# SSCI_SPI_LCD.net
KiCad netlist of a schematic drawn in EAGLE
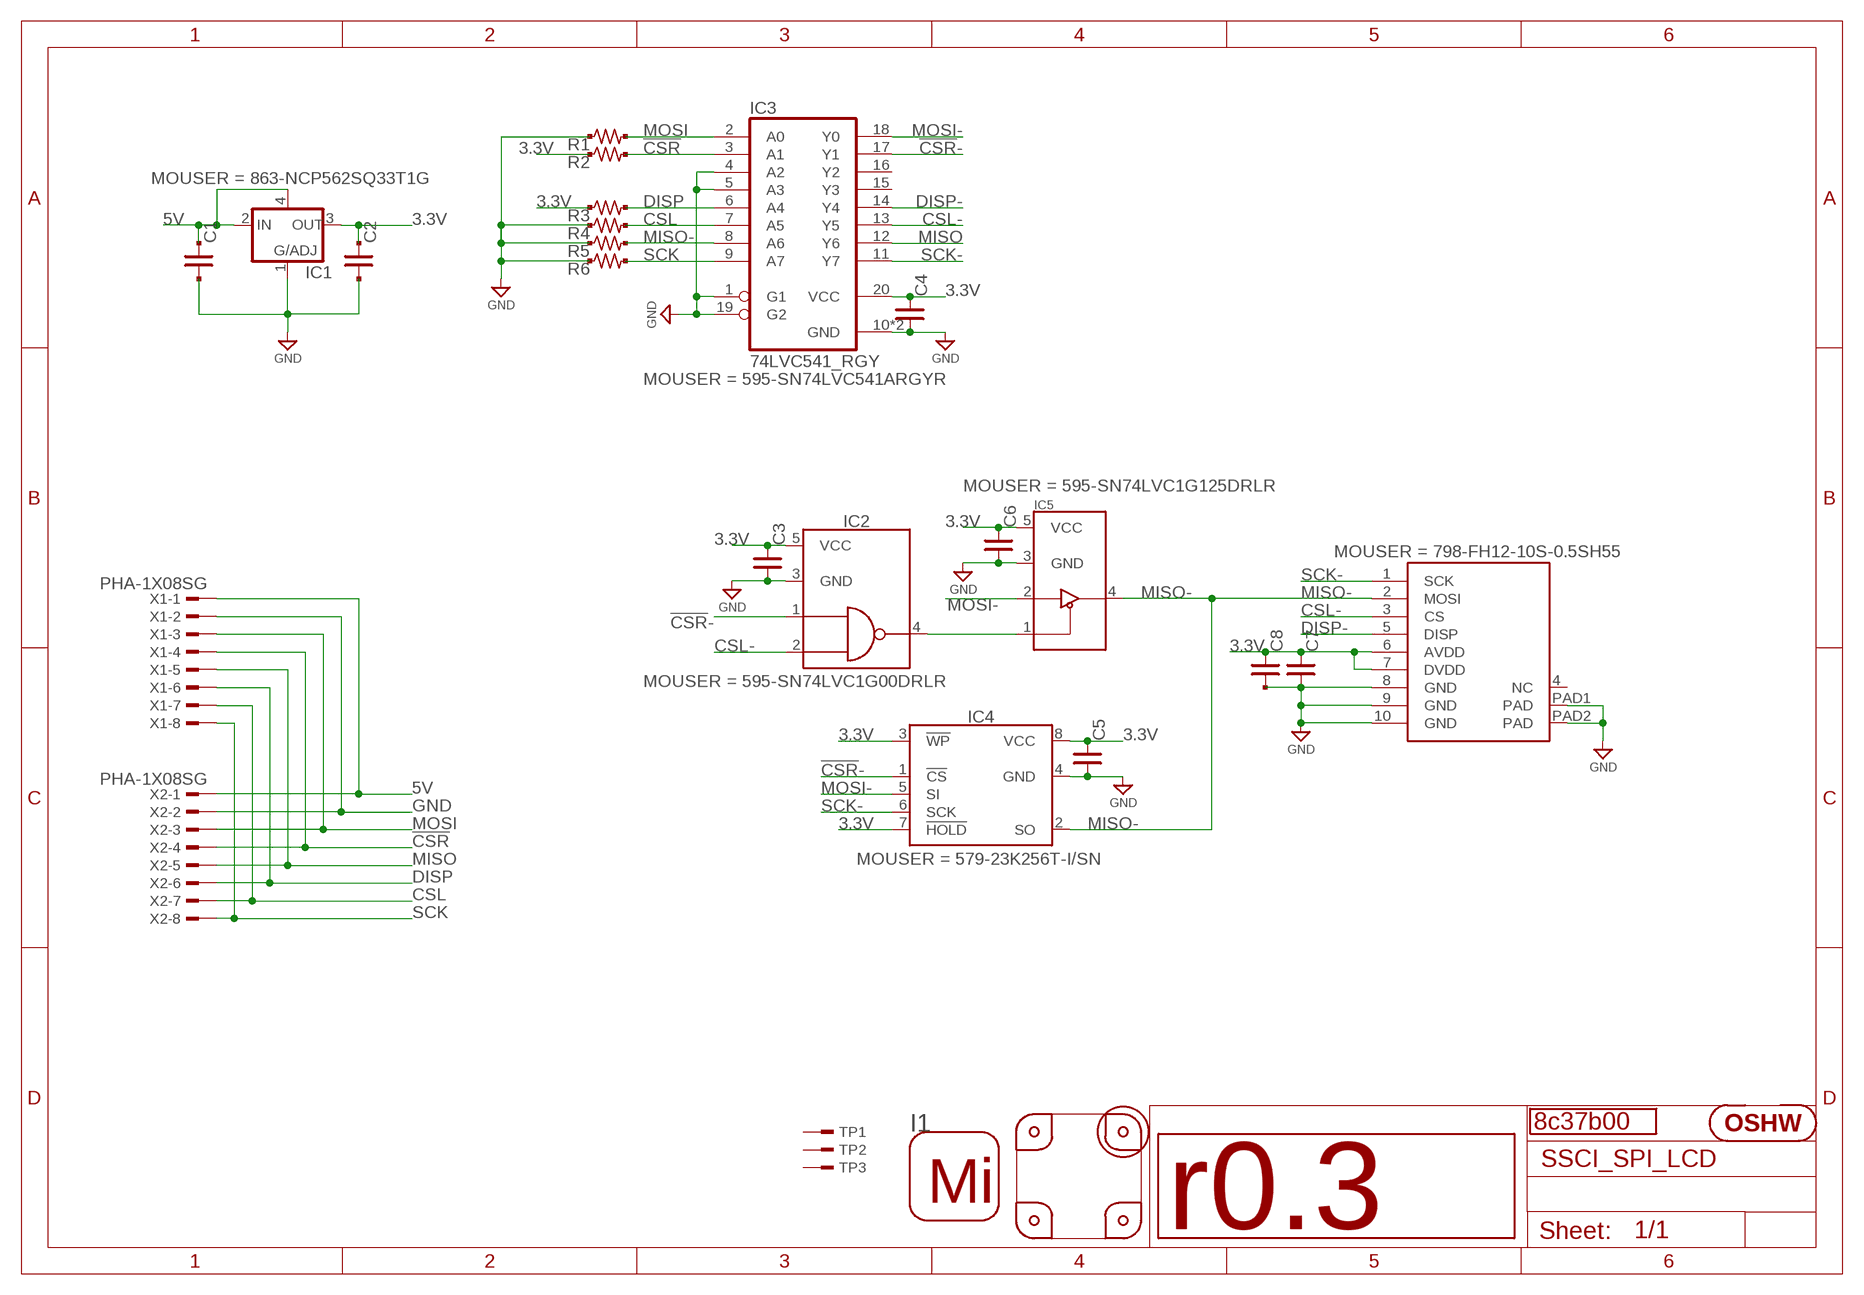
[diagram p0: schematic, sheet 1]

(export (version "E")
  (design (tool "Eeschema 10.0.6"))
  (components
    (comp (ref "C1")
      (value "C_SMD_10U_1608")
      (footprint "eagle-import:CR_1608")
      (libsource (lib "eagle-import") (part "C_SMD__160810U"))
    )
    (comp (ref "C2")
      (value "C_SMD_10U_1608")
      (footprint "eagle-import:CR_1608")
      (libsource (lib "eagle-import") (part "C_SMD__160810U"))
    )
    (comp (ref "C3")
      (value "C_SMD_0.1U_1005")
      (footprint "eagle-import:C0402")
      (libsource (lib "eagle-import") (part "C_SMD__10050.1U"))
    )
    (comp (ref "C4")
      (value "C_SMD_0.1U_1005")
      (footprint "eagle-import:C0402")
      (libsource (lib "eagle-import") (part "C_SMD__10050.1U"))
    )
    (comp (ref "C5")
      (value "C_SMD_0.1U_1005")
      (footprint "eagle-import:C0402")
      (libsource (lib "eagle-import") (part "C_SMD__10050.1U"))
    )
    (comp (ref "C6")
      (value "C_SMD_0.1U_1005")
      (footprint "eagle-import:C0402")
      (libsource (lib "eagle-import") (part "C_SMD__10050.1U"))
    )
    (comp (ref "C7")
      (value "C_SMD_0.1U_1005")
      (footprint "eagle-import:C0402")
      (libsource (lib "eagle-import") (part "C_SMD__10050.1U"))
    )
    (comp (ref "C8")
      (value "C_SMD_0.1U_1005")
      (footprint "eagle-import:C0402")
      (libsource (lib "eagle-import") (part "C_SMD__10050.1U"))
    )
    (comp (ref "GIT1")
      (value "8c37b00")
      (footprint "eagle-import:GIT-REVISION_1.2")
      (libsource (lib "eagle-import") (part "GIT-REVISION_1.2"))
    )
    (comp (ref "I1")
      (value "ICON_MINLAB_5.2S")
      (footprint "eagle-import:ICON_MINLAB_5.2MM")
      (libsource (lib "eagle-import") (part "ICON_MINLAB_5.2S"))
    )
    (comp (ref "IC1")
      (value "LDO4_3.3_SC82-AB")
      (footprint "eagle-import:SOT130P220X135-4N")
      (fields (field (name "MOUSER") "863-NCP562SQ33T1G"))
      (libsource (lib "eagle-import") (part "LDO4__SC82-AB3.3"))
    )
    (comp (ref "IC2")
      (value "74LVC1G00_DRL")
      (footprint "eagle-import:SOT50P160X120-5N")
      (fields (field (name "MOUSER") "595-SN74LVC1G00DRLR"))
      (libsource (lib "eagle-import") (part "741G00_DRLLVC"))
    )
    (comp (ref "IC3")
      (value "74LVC541_RGY")
      (footprint "eagle-import:QFN50P460X360-20N")
      (fields (field (name "MOUSER") "595-SN74LVC541ARGYR"))
      (libsource (lib "eagle-import") (part "74541_RGYLVC"))
    )
    (comp (ref "IC4")
      (value "IC_MEMORY_8P_23K256-I_SOP")
      (footprint "eagle-import:IC_08_1.27_150MIL")
      (fields (field (name "MOUSER") "579-23K256T-I/SN"))
      (libsource (lib "eagle-import") (part "IC_MEMORY_8P__SOP23K256-I"))
    )
    (comp (ref "IC5")
      (value "74LVC1G125_DRL")
      (footprint "eagle-import:SOT50P160X120-5N")
      (fields (field (name "MOUSER") "595-SN74LVC1G125DRLR"))
      (libsource (lib "eagle-import") (part "741G125_DRLLVC"))
    )
    (comp (ref "ICON1")
      (value "r0.3")
      (footprint "eagle-import:ICON_REVISION1.7")
      (libsource (lib "eagle-import") (part "ICON_REVISION_1.7"))
    )
    (comp (ref "ICON2")
      (value "ICON_OSHW")
      (footprint "eagle-import:ICON_OSHW")
      (libsource (lib "eagle-import") (part "ICON_OSHW"))
    )
    (comp (ref "LCD1")
      (value "LCD_GLCD_400X240")
      (footprint "eagle-import:LCD_GLCD_400X240")
      (fields (field (name "MOUSER") "798-FH12-10S-0.5SH55"))
      (libsource (lib "eagle-import") (part "LCD_GLCD_400X240"))
    )
    (comp (ref "P1")
      (value "PCB_CORNER_NH")
      (footprint "eagle-import:PCB_CORNER_NH")
      (libsource (lib "eagle-import") (part "PCB_CORNER_NH"))
    )
    (comp (ref "P2")
      (value "PCB_CORNER_NH")
      (footprint "eagle-import:PCB_CORNER_NH")
      (libsource (lib "eagle-import") (part "PCB_CORNER_NH"))
    )
    (comp (ref "P3")
      (value "PCB_CORNER_NH")
      (footprint "eagle-import:PCB_CORNER_NH")
      (libsource (lib "eagle-import") (part "PCB_CORNER_NH"))
    )
    (comp (ref "P4")
      (value "PCB_CORNER_NH")
      (footprint "eagle-import:PCB_CORNER_NH")
      (libsource (lib "eagle-import") (part "PCB_CORNER_NH"))
    )
    (comp (ref "R1")
      (value "R_US_10K_1005")
      (footprint "eagle-import:C0402")
      (libsource (lib "eagle-import") (part "R_US__100510K"))
    )
    (comp (ref "R2")
      (value "R_US_10K_1005")
      (footprint "eagle-import:C0402")
      (libsource (lib "eagle-import") (part "R_US__100510K"))
    )
    (comp (ref "R3")
      (value "R_US_10K_1005")
      (footprint "eagle-import:C0402")
      (libsource (lib "eagle-import") (part "R_US__100510K"))
    )
    (comp (ref "R4")
      (value "R_US_10K_1005")
      (footprint "eagle-import:C0402")
      (libsource (lib "eagle-import") (part "R_US__100510K"))
    )
    (comp (ref "R5")
      (value "R_US_10K_1005")
      (footprint "eagle-import:C0402")
      (libsource (lib "eagle-import") (part "R_US__100510K"))
    )
    (comp (ref "R6")
      (value "R_US_10K_1005")
      (footprint "eagle-import:C0402")
      (libsource (lib "eagle-import") (part "R_US__100510K"))
    )
    (comp (ref "TP1")
      (value "TESTPAD_F")
      (footprint "eagle-import:FIDUCIAL")
      (libsource (lib "eagle-import") (part "TESTPAD_F"))
    )
    (comp (ref "TP2")
      (value "TESTPAD_F")
      (footprint "eagle-import:FIDUCIAL")
      (libsource (lib "eagle-import") (part "TESTPAD_F"))
    )
    (comp (ref "TP3")
      (value "TESTPAD_F")
      (footprint "eagle-import:FIDUCIAL")
      (libsource (lib "eagle-import") (part "TESTPAD_F"))
    )
    (comp (ref "X1")
      (value "PHA-1X08SG")
      (footprint "eagle-import:PHA-1X08SG")
      (libsource (lib "eagle-import") (part "PHA-1X08GS"))
    )
    (comp (ref "X2")
      (value "PHA-1X08SG")
      (footprint "eagle-import:PHA-1X08SG")
      (libsource (lib "eagle-import") (part "PHA-1X08GS"))
    )
  )
  (nets
    (net (code "1") (name "/3.3V") (class "Default")
      (node (ref "C2") (pin "1") (pinfunction "1_1") (pintype "passive"))
      (node (ref "C3") (pin "1") (pinfunction "1_1") (pintype "passive"))
      (node (ref "C4") (pin "1") (pinfunction "1_1") (pintype "passive"))
      (node (ref "C5") (pin "1") (pinfunction "1_1") (pintype "passive"))
      (node (ref "C6") (pin "1") (pinfunction "1_1") (pintype "passive"))
      (node (ref "C7") (pin "1") (pinfunction "1_1") (pintype "passive"))
      (node (ref "C8") (pin "1") (pinfunction "1_1") (pintype "passive"))
      (node (ref "IC1") (pin "3") (pinfunction "OUT_3") (pintype "power_in"))
      (node (ref "IC2") (pin "5") (pinfunction "VCC_5") (pintype "power_in"))
      (node (ref "IC3") (pin "20") (pinfunction "VCC_20") (pintype "power_in"))
      (node (ref "IC4") (pin "3") (pinfunction "~{WP}_3") (pintype "input"))
      (node (ref "IC4") (pin "7") (pinfunction "~{HOLD}_7") (pintype "input"))
      (node (ref "IC4") (pin "8") (pinfunction "VCC_8") (pintype "power_in"))
      (node (ref "IC5") (pin "5") (pinfunction "VCC_5") (pintype "power_in"))
      (node (ref "LCD1") (pin "6") (pinfunction "AVDD_6") (pintype "bidirectional"))
      (node (ref "LCD1") (pin "7") (pinfunction "DVDD_7") (pintype "bidirectional"))
      (node (ref "R2") (pin "1") (pinfunction "1_1") (pintype "passive"))
      (node (ref "R3") (pin "1") (pinfunction "1_1") (pintype "passive"))
    )
    (net (code "2") (name "/5V") (class "Default")
      (node (ref "C1") (pin "1") (pinfunction "1_1") (pintype "passive"))
      (node (ref "IC1") (pin "2") (pinfunction "IN_2") (pintype "power_in"))
      (node (ref "IC1") (pin "4") (pinfunction "OUT/EN/NC_4") (pintype "tri_state"))
      (node (ref "X1") (pin "1") (pinfunction "1_1") (pintype "passive"))
      (node (ref "X2") (pin "1") (pinfunction "1_1") (pintype "passive"))
    )
    (net (code "3") (name "/CSL") (class "Default")
      (node (ref "IC3") (pin "7") (pinfunction "A5_7") (pintype "input"))
      (node (ref "R4") (pin "2") (pinfunction "2_2") (pintype "passive"))
      (node (ref "X1") (pin "7") (pinfunction "1_7") (pintype "passive"))
      (node (ref "X2") (pin "7") (pinfunction "1_7") (pintype "passive"))
    )
    (net (code "4") (name "/CSL-") (class "Default")
      (node (ref "IC2") (pin "2") (pinfunction "1B_2") (pintype "input"))
      (node (ref "IC3") (pin "13") (pinfunction "Y5_13") (pintype "output"))
      (node (ref "LCD1") (pin "3") (pinfunction "CS_3") (pintype "bidirectional"))
    )
    (net (code "5") (name "/DISP") (class "Default")
      (node (ref "IC3") (pin "6") (pinfunction "A4_6") (pintype "input"))
      (node (ref "R3") (pin "2") (pinfunction "2_2") (pintype "passive"))
      (node (ref "X1") (pin "6") (pinfunction "1_6") (pintype "passive"))
      (node (ref "X2") (pin "6") (pinfunction "1_6") (pintype "passive"))
    )
    (net (code "6") (name "/DISP-") (class "Default")
      (node (ref "IC3") (pin "14") (pinfunction "Y4_14") (pintype "output"))
      (node (ref "LCD1") (pin "5") (pinfunction "DISP_5") (pintype "bidirectional"))
    )
    (net (code "7") (name "/MISO") (class "Default")
      (node (ref "IC3") (pin "12") (pinfunction "Y6_12") (pintype "output"))
      (node (ref "X1") (pin "5") (pinfunction "1_5") (pintype "passive"))
      (node (ref "X2") (pin "5") (pinfunction "1_5") (pintype "passive"))
    )
    (net (code "8") (name "/MISO-") (class "Default")
      (node (ref "IC3") (pin "8") (pinfunction "A6_8") (pintype "input"))
      (node (ref "IC4") (pin "2") (pinfunction "SO_2") (pintype "output"))
      (node (ref "IC5") (pin "4") (pinfunction "Y_4") (pintype "output"))
      (node (ref "LCD1") (pin "2") (pinfunction "MOSI_2") (pintype "bidirectional"))
      (node (ref "R5") (pin "2") (pinfunction "2_2") (pintype "passive"))
    )
    (net (code "9") (name "/MOSI") (class "Default")
      (node (ref "IC3") (pin "2") (pinfunction "A0_2") (pintype "input"))
      (node (ref "R1") (pin "2") (pinfunction "2_2") (pintype "passive"))
      (node (ref "X1") (pin "3") (pinfunction "1_3") (pintype "passive"))
      (node (ref "X2") (pin "3") (pinfunction "1_3") (pintype "passive"))
    )
    (net (code "10") (name "/MOSI-") (class "Default")
      (node (ref "IC3") (pin "18") (pinfunction "Y0_18") (pintype "output"))
      (node (ref "IC4") (pin "5") (pinfunction "SI_5") (pintype "input"))
      (node (ref "IC5") (pin "2") (pinfunction "A_2") (pintype "input"))
    )
    (net (code "11") (name "/SCK") (class "Default")
      (node (ref "IC3") (pin "9") (pinfunction "A7_9") (pintype "input"))
      (node (ref "R6") (pin "2") (pinfunction "2_2") (pintype "passive"))
      (node (ref "X1") (pin "8") (pinfunction "1_8") (pintype "passive"))
      (node (ref "X2") (pin "8") (pinfunction "1_8") (pintype "passive"))
    )
    (net (code "12") (name "/SCK-") (class "Default")
      (node (ref "IC3") (pin "11") (pinfunction "Y7_11") (pintype "output"))
      (node (ref "IC4") (pin "6") (pinfunction "SCK_6") (pintype "input"))
      (node (ref "LCD1") (pin "1") (pinfunction "SCK_1") (pintype "bidirectional"))
    )
    (net (code "13") (name "/~{CSR}") (class "Default")
      (node (ref "IC3") (pin "3") (pinfunction "A1_3") (pintype "input"))
      (node (ref "R2") (pin "2") (pinfunction "2_2") (pintype "passive"))
      (node (ref "X1") (pin "4") (pinfunction "1_4") (pintype "passive"))
      (node (ref "X2") (pin "4") (pinfunction "1_4") (pintype "passive"))
    )
    (net (code "14") (name "/~{CSR}-") (class "Default")
      (node (ref "IC2") (pin "1") (pinfunction "1A_1") (pintype "input"))
      (node (ref "IC3") (pin "17") (pinfunction "Y1_17") (pintype "output"))
      (node (ref "IC4") (pin "1") (pinfunction "~{CS}_1") (pintype "input"))
    )
    (net (code "15") (name "GND") (class "Default")
      (node (ref "C1") (pin "2") (pinfunction "2_2") (pintype "passive"))
      (node (ref "C2") (pin "2") (pinfunction "2_2") (pintype "passive"))
      (node (ref "C3") (pin "2") (pinfunction "2_2") (pintype "passive"))
      (node (ref "C4") (pin "2") (pinfunction "2_2") (pintype "passive"))
      (node (ref "C5") (pin "2") (pinfunction "2_2") (pintype "passive"))
      (node (ref "C6") (pin "2") (pinfunction "2_2") (pintype "passive"))
      (node (ref "C7") (pin "2") (pinfunction "2_2") (pintype "passive"))
      (node (ref "C8") (pin "2") (pinfunction "2_2") (pintype "passive"))
      (node (ref "IC1") (pin "1") (pinfunction "ADJ_1") (pintype "power_in"))
      (node (ref "IC2") (pin "3") (pinfunction "GND_3") (pintype "power_in"))
      (node (ref "IC3") (pin "1") (pinfunction "G1_1") (pintype "input"))
      (node (ref "IC3") (pin "10") (pinfunction "GND_10") (pintype "power_in"))
      (node (ref "IC3") (pin "19") (pinfunction "G2_19") (pintype "input"))
      (node (ref "IC3") (pin "4") (pinfunction "A2_4") (pintype "input"))
      (node (ref "IC3") (pin "5") (pinfunction "A3_5") (pintype "input"))
      (node (ref "IC3") (pin "EP") (pinfunction "GND_EP") (pintype "power_in"))
      (node (ref "IC4") (pin "4") (pinfunction "GND_4") (pintype "power_in"))
      (node (ref "IC5") (pin "3") (pinfunction "GND_3") (pintype "power_in"))
      (node (ref "LCD1") (pin "10") (pinfunction "GND_10") (pintype "bidirectional"))
      (node (ref "LCD1") (pin "8") (pinfunction "GND_8") (pintype "bidirectional"))
      (node (ref "LCD1") (pin "9") (pinfunction "GND_9") (pintype "bidirectional"))
      (node (ref "LCD1") (pin "PAD1") (pinfunction "PAD_PAD1") (pintype "bidirectional"))
      (node (ref "LCD1") (pin "PAD2") (pinfunction "PAD_PAD2") (pintype "bidirectional"))
      (node (ref "R1") (pin "1") (pinfunction "1_1") (pintype "passive"))
      (node (ref "R4") (pin "1") (pinfunction "1_1") (pintype "passive"))
      (node (ref "R5") (pin "1") (pinfunction "1_1") (pintype "passive"))
      (node (ref "R6") (pin "1") (pinfunction "1_1") (pintype "passive"))
      (node (ref "X1") (pin "2") (pinfunction "1_2") (pintype "passive"))
      (node (ref "X2") (pin "2") (pinfunction "1_2") (pintype "passive"))
    )
    (net (code "16") (name "Net-(IC2-1Y)") (class "Default")
      (node (ref "IC2") (pin "4") (pinfunction "1Y_4") (pintype "output"))
      (node (ref "IC5") (pin "1") (pinfunction "~{OE}_1") (pintype "input"))
    )
    (net (code "17") (name "unconnected-(IC3-Y2-Pad16)") (class "Default")
      (node (ref "IC3") (pin "16") (pinfunction "Y2_16") (pintype "output"))
    )
    (net (code "18") (name "unconnected-(IC3-Y3-Pad15)") (class "Default")
      (node (ref "IC3") (pin "15") (pinfunction "Y3_15") (pintype "output"))
    )
    (net (code "19") (name "unconnected-(LCD1-NC-Pad4)") (class "Default")
      (node (ref "LCD1") (pin "4") (pinfunction "NC_4") (pintype "bidirectional"))
    )
    (net (code "20") (name "unconnected-(TP1-1-PadTP)") (class "Default")
      (node (ref "TP1") (pin "TP") (pinfunction "1_TP") (pintype "passive"))
    )
    (net (code "21") (name "unconnected-(TP2-1-PadTP)") (class "Default")
      (node (ref "TP2") (pin "TP") (pinfunction "1_TP") (pintype "passive"))
    )
    (net (code "22") (name "unconnected-(TP3-1-PadTP)") (class "Default")
      (node (ref "TP3") (pin "TP") (pinfunction "1_TP") (pintype "passive"))
    )
  )
)
